# Peltie.net
KiCad netlist of a schematic drawn in Altium Designer
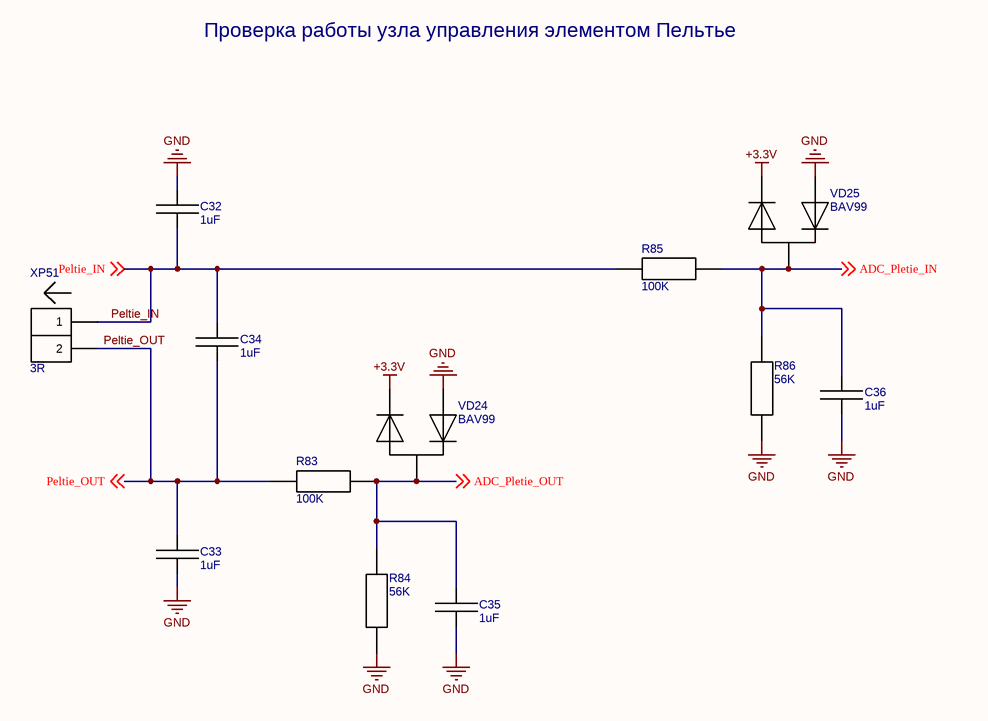
[diagram p0: Peltie.SchDoc]

(export (version "E")
  (design (tool "Eeschema 10.0.6"))
  (components
    (comp (ref "C32")
      (value "1uF")
      (footprint "0603C")
      (description "C0603-1uF 10% 50V")
      (fields
        (field (name "PART NUMBER") "SMD CAP CER 1uF ±10% 50V X7R 0603")
        (field (name "ADDED_BY") "grebelny_av@teslatec.ru")
      )
      (libsource (lib "Test_Stand_Pergam") (part "C0603-1uF 10% 50V"))
    )
    (comp (ref "C33")
      (value "1uF")
      (footprint "0603C")
      (description "C0603-1uF 10% 50V")
      (fields
        (field (name "PART NUMBER") "SMD CAP CER 1uF ±10% 50V X7R 0603")
        (field (name "ADDED_BY") "grebelny_av@teslatec.ru")
      )
      (libsource (lib "Test_Stand_Pergam") (part "C0603-1uF 10% 50V"))
    )
    (comp (ref "C34")
      (value "1uF")
      (footprint "0603C")
      (description "C0603-1uF 10% 50V")
      (fields
        (field (name "PART NUMBER") "SMD CAP CER 1uF ±10% 50V X7R 0603")
        (field (name "ADDED_BY") "grebelny_av@teslatec.ru")
      )
      (libsource (lib "Test_Stand_Pergam") (part "C0603-1uF 10% 50V"))
    )
    (comp (ref "C35")
      (value "1uF")
      (footprint "0603C")
      (description "C0603-1uF 10% 50V")
      (fields
        (field (name "PART NUMBER") "SMD CAP CER 1uF ±10% 50V X7R 0603")
        (field (name "ADDED_BY") "grebelny_av@teslatec.ru")
      )
      (libsource (lib "Test_Stand_Pergam") (part "C0603-1uF 10% 50V"))
    )
    (comp (ref "C36")
      (value "1uF")
      (footprint "0603C")
      (description "C0603-1uF 10% 50V")
      (fields
        (field (name "PART NUMBER") "SMD CAP CER 1uF ±10% 50V X7R 0603")
        (field (name "ADDED_BY") "grebelny_av@teslatec.ru")
      )
      (libsource (lib "Test_Stand_Pergam") (part "C0603-1uF 10% 50V"))
    )
    (comp (ref "R83")
      (value "100K")
      (footprint "R0402")
      (description "Resistor SMD 100K 1% 0402")
      (fields
        (field (name "PART NUMBER") "SMD RES 100 KOHM 1% ±100ppm/°C 0402")
        (field (name "ADDED_BY") "Rutel@teslatec.ru")
      )
      (libsource (lib "Test_Stand_Pergam") (part "R0402-100K"))
    )
    (comp (ref "R84")
      (value "56K")
      (footprint "R0402")
      (description "Resistor SMD 56K 1% 0402")
      (fields
        (field (name "PART NUMBER") "SMD RES 56K KOHM 1% ±100ppm/°C 0402")
        (field (name "ADDED_BY") "ridel_av@teslatec.ru")
      )
      (libsource (lib "Test_Stand_Pergam") (part "R0402-56K"))
    )
    (comp (ref "R85")
      (value "100K")
      (footprint "R0402")
      (description "Resistor SMD 100K 1% 0402")
      (fields
        (field (name "PART NUMBER") "SMD RES 100 KOHM 1% ±100ppm/°C 0402")
        (field (name "ADDED_BY") "Rutel@teslatec.ru")
      )
      (libsource (lib "Test_Stand_Pergam") (part "R0402-100K"))
    )
    (comp (ref "R86")
      (value "56K")
      (footprint "R0402")
      (description "Resistor SMD 56K 1% 0402")
      (fields
        (field (name "PART NUMBER") "SMD RES 56K KOHM 1% ±100ppm/°C 0402")
        (field (name "ADDED_BY") "ridel_av@teslatec.ru")
      )
      (libsource (lib "Test_Stand_Pergam") (part "R0402-56K"))
    )
    (comp (ref "VD24")
      (value "BAV99")
      (footprint "SOT-23-3")
      (description "BAV99, UMW, 70В, 200мА")
      (fields (field (name "ADDED_BY") "andrew@teslatec.ru"))
      (libsource (lib "Test_Stand_Pergam") (part "BAV99"))
    )
    (comp (ref "VD25")
      (value "BAV99")
      (footprint "SOT-23-3")
      (description "BAV99, UMW, 70В, 200мА")
      (fields (field (name "ADDED_BY") "andrew@teslatec.ru"))
      (libsource (lib "Test_Stand_Pergam") (part "BAV99"))
    )
    (comp (ref "XP51")
      (value "3R")
      (footprint "PLS-2")
      (description "SQP10AJB-3R")
      (fields (field (name "PART NUMBER") "PLS-2") (field (name "ADDED_BY") "irdolgopolowa@yandex.ru"))
      (libsource (lib "Test_Stand_Pergam") (part "PLS-2_peltie"))
    )
  )
  (nets
    (net (code "1") (name "+3.3V") (class "Default")
      (node (ref "VD24") (pin "2") (pinfunction "2_2") (pintype "passive"))
      (node (ref "VD25") (pin "2") (pinfunction "2_2") (pintype "passive"))
    )
    (net (code "2") (name "ADC_Pletie_IN") (class "Default")
      (node (ref "C36") (pin "2") (pinfunction "2_2") (pintype "passive"))
      (node (ref "R85") (pin "1") (pinfunction "1_1") (pintype "passive"))
      (node (ref "R86") (pin "1") (pinfunction "1_1") (pintype "passive"))
      (node (ref "VD25") (pin "3") (pinfunction "3_3") (pintype "passive"))
    )
    (net (code "3") (name "ADC_Pletie_OUT") (class "Default")
      (node (ref "C35") (pin "2") (pinfunction "2_2") (pintype "passive"))
      (node (ref "R83") (pin "1") (pinfunction "1_1") (pintype "passive"))
      (node (ref "R84") (pin "1") (pinfunction "1_1") (pintype "passive"))
      (node (ref "VD24") (pin "3") (pinfunction "3_3") (pintype "passive"))
    )
    (net (code "4") (name "GND") (class "Default")
      (node (ref "C32") (pin "2") (pinfunction "2_2") (pintype "passive"))
      (node (ref "C33") (pin "2") (pinfunction "2_2") (pintype "passive"))
      (node (ref "C35") (pin "1") (pinfunction "1_1") (pintype "passive"))
      (node (ref "C36") (pin "1") (pinfunction "1_1") (pintype "passive"))
      (node (ref "R84") (pin "2") (pinfunction "2_2") (pintype "passive"))
      (node (ref "R86") (pin "2") (pinfunction "2_2") (pintype "passive"))
      (node (ref "VD24") (pin "1") (pinfunction "1_1") (pintype "passive"))
      (node (ref "VD25") (pin "1") (pinfunction "1_1") (pintype "passive"))
    )
    (net (code "5") (name "Peltie_IN") (class "Default")
      (node (ref "C32") (pin "1") (pinfunction "1_1") (pintype "passive"))
      (node (ref "C34") (pin "2") (pinfunction "2_2") (pintype "passive"))
      (node (ref "R85") (pin "2") (pinfunction "2_2") (pintype "passive"))
      (node (ref "XP51") (pin "1") (pinfunction "1_1") (pintype "passive"))
    )
    (net (code "6") (name "Peltie_OUT") (class "Default")
      (node (ref "C33") (pin "1") (pinfunction "1_1") (pintype "passive"))
      (node (ref "C34") (pin "1") (pinfunction "1_1") (pintype "passive"))
      (node (ref "R83") (pin "2") (pinfunction "2_2") (pintype "passive"))
      (node (ref "XP51") (pin "2") (pinfunction "2_2") (pintype "passive"))
    )
  )
)
